# Peripherals.net
KiCad netlist of a schematic drawn in Altium Designer
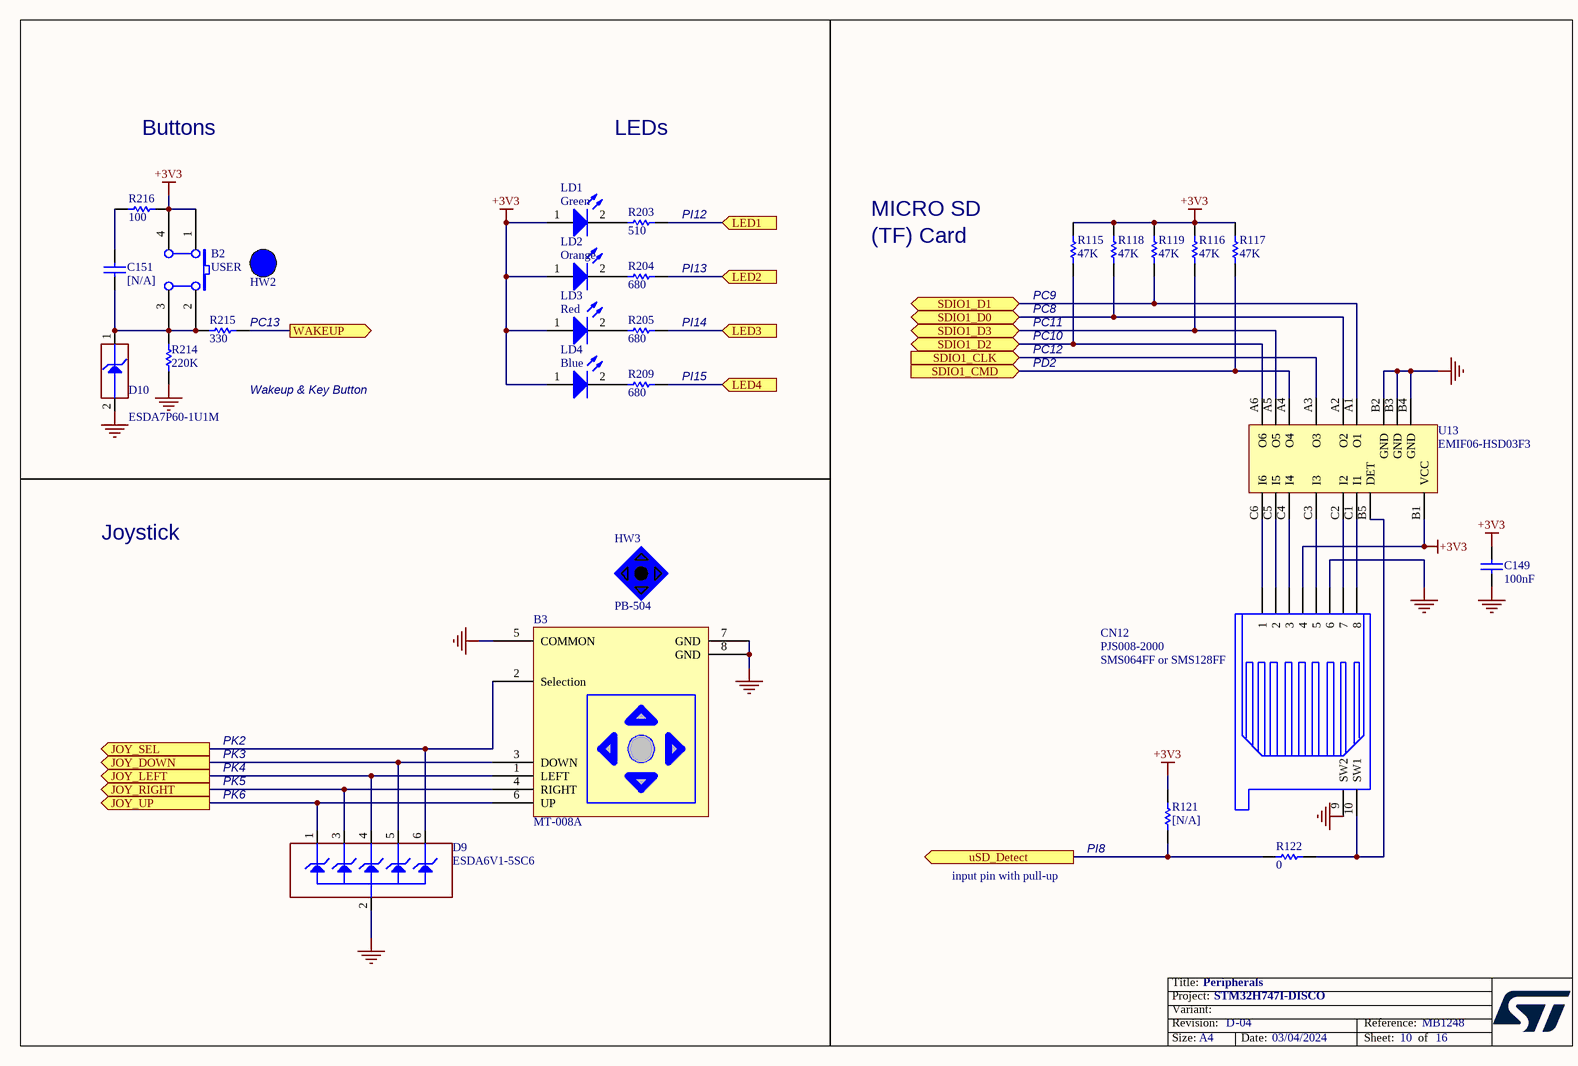
[diagram p0: Peripherals.SchDoc]

(export (version "E")
  (design (tool "Eeschema 10.0.6"))
  (components
    (comp (ref "B2")
      (value "USER")
      (footprint "PB10")
      (description "SE PUSHBUTTON")
      (libsource (lib "Documents") (part "SW PUSHBUTTON"))
    )
    (comp (ref "B3") (value "MT-008A") (footprint "MT-008A") (libsource (lib "MB1248") (part "MT-008A")))
    (comp (ref "C149")
      (value "100nF")
      (footprint "0603C")
      (description "Capacitor")
      (fields (field (name "PUBLISHER") "Altium Limited"))
      (libsource (lib "Miscellaneous Devices") (part "CAP"))
    )
    (comp (ref "C151")
      (value "[N/A]")
      (footprint "0603C")
      (description "Capacitor")
      (fields (field (name "PUBLISHER") "Altium Limited"))
      (libsource (lib "Miscellaneous Devices") (part "cap"))
    )
    (comp (ref "CN12")
      (value "PJS008-2000")
      (footprint "MSD_PJS008_")
      (libsource (lib "MB525") (part "SMS016AFA5E"))
    )
    (comp (ref "D9")
      (value "ESDA6V1-5SC6")
      (footprint "STM-SMEE:SOT23-6L")
      (description "5-line ESD protection")
      (libsource (lib "MB1248_1") (part "ESDA6V1-5SC6"))
    )
    (comp (ref "D10")
      (value "ESDA7P60-1U1M")
      (footprint "DO_2SM_1R6X1_21")
      (description "Dual Transil array for ESD protection")
      (libsource (lib "MCD_TEMP_PCH") (part "ESDALC6V1-1U2"))
    )
    (comp (ref "HW2") (value "BUTTON_HAT_BLUE") (libsource (lib "Schlib1") (part "BUTTON_HAT_BLUE")))
    (comp (ref "HW3")
      (value "PB-504")
      (description "Joystick, Blue hat")
      (fields (field (name "INTERNAL_PART_NUMBER") "MCD-01337") (field (name "MANUFACTURER") "JIUBABA"))
      (libsource (lib "MCD_PARTS_database") (part "JOYSTICK_BLUE_HAT"))
    )
    (comp (ref "LD1")
      (value "Green")
      (footprint "0603D")
      (description "Typical RED, GREEN, YELLOW, AMBER GaAs LED")
      (fields (field (name "PUBLISHER") "Altium Limited"))
      (libsource (lib "Miscellaneous Devices") (part "LED2"))
    )
    (comp (ref "LD2")
      (value "Orange")
      (footprint "0603D")
      (description "Typical RED, GREEN, YELLOW, AMBER GaAs LED")
      (fields (field (name "PUBLISHER") "Altium Limited"))
      (libsource (lib "Miscellaneous Devices") (part "LED2"))
    )
    (comp (ref "LD3")
      (value "Red")
      (footprint "0603D")
      (description "Typical RED, GREEN, YELLOW, AMBER GaAs LED")
      (fields (field (name "PUBLISHER") "Altium Limited"))
      (libsource (lib "Miscellaneous Devices") (part "LED2"))
    )
    (comp (ref "LD4")
      (value "Blue")
      (footprint "0603D")
      (description "Typical RED, GREEN, YELLOW, AMBER GaAs LED")
      (fields (field (name "PUBLISHER") "Altium Limited"))
      (libsource (lib "Miscellaneous Devices") (part "LED2"))
    )
    (comp (ref "R115")
      (value "47K")
      (footprint "0603R")
      (description "Resistor")
      (fields (field (name "PUBLISHER") "Altium Limited"))
      (libsource (lib "Miscellaneous Devices") (part "res1"))
    )
    (comp (ref "R116")
      (value "47K")
      (footprint "0603R")
      (description "Resistor")
      (fields (field (name "PUBLISHER") "Altium Limited"))
      (libsource (lib "Miscellaneous Devices") (part "res1"))
    )
    (comp (ref "R117")
      (value "47K")
      (footprint "0603R")
      (description "Resistor")
      (fields (field (name "PUBLISHER") "Altium Limited"))
      (libsource (lib "Miscellaneous Devices") (part "res1"))
    )
    (comp (ref "R118")
      (value "47K")
      (footprint "0603R")
      (description "Resistor")
      (fields (field (name "PUBLISHER") "Altium Limited"))
      (libsource (lib "Miscellaneous Devices") (part "res1"))
    )
    (comp (ref "R119")
      (value "47K")
      (footprint "0603R")
      (description "Resistor")
      (fields (field (name "PUBLISHER") "Altium Limited"))
      (libsource (lib "Miscellaneous Devices") (part "res1"))
    )
    (comp (ref "R121")
      (value "[N/A]")
      (footprint "0603R")
      (description "Resistor")
      (fields (field (name "PUBLISHER") "Altium Limited"))
      (libsource (lib "Miscellaneous Devices") (part "res1"))
    )
    (comp (ref "R122")
      (value "0")
      (footprint "0603R")
      (description "Resistor")
      (fields (field (name "PUBLISHER") "Altium Limited"))
      (libsource (lib "Miscellaneous Devices") (part "Res1"))
    )
    (comp (ref "R203")
      (value "510")
      (footprint "0603R")
      (description "Resistor")
      (fields (field (name "PUBLISHER") "Altium Limited"))
      (libsource (lib "Miscellaneous Devices") (part "Res1"))
    )
    (comp (ref "R204")
      (value "680")
      (footprint "0603R")
      (description "Resistor")
      (fields (field (name "PUBLISHER") "Altium Limited"))
      (libsource (lib "Miscellaneous Devices") (part "Res1"))
    )
    (comp (ref "R205")
      (value "680")
      (footprint "0603R")
      (description "Resistor")
      (fields (field (name "PUBLISHER") "Altium Limited"))
      (libsource (lib "Miscellaneous Devices") (part "Res1"))
    )
    (comp (ref "R209")
      (value "680")
      (footprint "0603R")
      (description "Resistor")
      (fields (field (name "PUBLISHER") "Altium Limited"))
      (libsource (lib "Miscellaneous Devices") (part "Res1"))
    )
    (comp (ref "R214")
      (value "220K")
      (footprint "0603R")
      (description "Resistor")
      (fields (field (name "PUBLISHER") "Altium Limited"))
      (libsource (lib "Miscellaneous Devices") (part "res1"))
    )
    (comp (ref "R215")
      (value "330")
      (footprint "0603R")
      (description "Resistor")
      (fields (field (name "PUBLISHER") "Altium Limited"))
      (libsource (lib "Miscellaneous Devices") (part "Res1"))
    )
    (comp (ref "R216")
      (value "100")
      (footprint "0603R")
      (description "Resistor")
      (fields (field (name "PUBLISHER") "Altium Limited"))
      (libsource (lib "Miscellaneous Devices") (part "Res1"))
    )
    (comp (ref "U13")
      (value "EMIF06-HSD03F3")
      (footprint "FBGA17_0R4_1R1X2R4")
      (description "EMI filter with integrated ESD protection for micro-SD Card™")
      (libsource (lib "MB1248_1") (part "EMIF06-HSD03F3"))
    )
  )
  (nets
    (net (code "1") (name "+3V3") (class "Default")
      (node (ref "B2") (pin "1") (pinfunction "A0_1") (pintype "passive"))
      (node (ref "B2") (pin "4") (pinfunction "A1_4") (pintype "passive"))
      (node (ref "C149") (pin "1") (pinfunction "1_1") (pintype "passive"))
      (node (ref "CN12") (pin "4") (pinfunction "4_4") (pintype "passive"))
      (node (ref "LD1") (pin "1") (pinfunction "A_1") (pintype "passive"))
      (node (ref "LD2") (pin "1") (pinfunction "A_1") (pintype "passive"))
      (node (ref "LD3") (pin "1") (pinfunction "A_1") (pintype "passive"))
      (node (ref "LD4") (pin "1") (pinfunction "A_1") (pintype "passive"))
      (node (ref "R115") (pin "1") (pinfunction "1_1") (pintype "passive"))
      (node (ref "R116") (pin "1") (pinfunction "1_1") (pintype "passive"))
      (node (ref "R117") (pin "1") (pinfunction "1_1") (pintype "passive"))
      (node (ref "R118") (pin "1") (pinfunction "1_1") (pintype "passive"))
      (node (ref "R119") (pin "1") (pinfunction "1_1") (pintype "passive"))
      (node (ref "R121") (pin "2") (pinfunction "2_2") (pintype "passive"))
      (node (ref "R216") (pin "1") (pinfunction "1_1") (pintype "passive"))
      (node (ref "U13") (pin "B1") (pinfunction "VCC_B1") (pintype "passive"))
    )
    (net (code "2") (name "/JOY_DOWN") (class "Default")
      (node (ref "B3") (pin "3") (pinfunction "DOWN_3") (pintype "passive"))
      (node (ref "D9") (pin "5") (pinfunction "IO4_5") (pintype "passive"))
    )
    (net (code "3") (name "/JOY_LEFT") (class "Default")
      (node (ref "B3") (pin "1") (pinfunction "LEFT_1") (pintype "passive"))
      (node (ref "D9") (pin "4") (pinfunction "IO3_4") (pintype "passive"))
    )
    (net (code "4") (name "/JOY_RIGHT") (class "Default")
      (node (ref "B3") (pin "4") (pinfunction "RIGHT_4") (pintype "passive"))
      (node (ref "D9") (pin "3") (pinfunction "IO2_3") (pintype "passive"))
    )
    (net (code "5") (name "/JOY_SEL") (class "Default")
      (node (ref "B3") (pin "2") (pinfunction "Selection_2") (pintype "passive"))
      (node (ref "D9") (pin "6") (pinfunction "IO5_6") (pintype "passive"))
    )
    (net (code "6") (name "/JOY_UP") (class "Default")
      (node (ref "B3") (pin "6") (pinfunction "UP_6") (pintype "passive"))
      (node (ref "D9") (pin "1") (pinfunction "IO1_1") (pintype "passive"))
    )
    (net (code "7") (name "/LED1") (class "Default")
      (node (ref "R203") (pin "1") (pinfunction "1_1") (pintype "passive"))
    )
    (net (code "8") (name "/LED2") (class "Default")
      (node (ref "R204") (pin "1") (pinfunction "1_1") (pintype "passive"))
    )
    (net (code "9") (name "/LED3") (class "Default")
      (node (ref "R205") (pin "1") (pinfunction "1_1") (pintype "passive"))
    )
    (net (code "10") (name "/LED4") (class "Default")
      (node (ref "R209") (pin "1") (pinfunction "1_1") (pintype "passive"))
    )
    (net (code "11") (name "/SDIO1_CLK") (class "Default")
      (node (ref "U13") (pin "A3") (pinfunction "O3_A3") (pintype "passive"))
    )
    (net (code "12") (name "/SDIO1_CMD") (class "Default")
      (node (ref "R117") (pin "2") (pinfunction "2_2") (pintype "passive"))
      (node (ref "U13") (pin "A4") (pinfunction "O4_A4") (pintype "passive"))
    )
    (net (code "13") (name "/SDIO1_D0") (class "Default")
      (node (ref "R118") (pin "2") (pinfunction "2_2") (pintype "passive"))
      (node (ref "U13") (pin "A2") (pinfunction "O2_A2") (pintype "passive"))
    )
    (net (code "14") (name "/SDIO1_D1") (class "Default")
      (node (ref "R119") (pin "2") (pinfunction "2_2") (pintype "passive"))
      (node (ref "U13") (pin "A1") (pinfunction "O1_A1") (pintype "passive"))
    )
    (net (code "15") (name "/SDIO1_D2") (class "Default")
      (node (ref "R115") (pin "2") (pinfunction "2_2") (pintype "passive"))
      (node (ref "U13") (pin "A6") (pinfunction "O6_A6") (pintype "passive"))
    )
    (net (code "16") (name "/SDIO1_D3") (class "Default")
      (node (ref "R116") (pin "2") (pinfunction "2_2") (pintype "passive"))
      (node (ref "U13") (pin "A5") (pinfunction "O5_A5") (pintype "passive"))
    )
    (net (code "17") (name "/WAKEUP") (class "Default")
      (node (ref "R215") (pin "2") (pinfunction "2_2") (pintype "passive"))
    )
    (net (code "18") (name "/uSD_Detect") (class "Default")
      (node (ref "R121") (pin "1") (pinfunction "1_1") (pintype "passive"))
      (node (ref "R122") (pin "1") (pinfunction "1_1") (pintype "passive"))
    )
    (net (code "19") (name "GND") (class "Default")
      (node (ref "B3") (pin "5") (pinfunction "COMMON_5") (pintype "passive"))
      (node (ref "B3") (pin "7") (pinfunction "GND_7") (pintype "passive"))
      (node (ref "B3") (pin "8") (pinfunction "GND_8") (pintype "passive"))
      (node (ref "C149") (pin "2") (pinfunction "2_2") (pintype "passive"))
      (node (ref "CN12") (pin "6") (pinfunction "6_6") (pintype "passive"))
      (node (ref "CN12") (pin "9") (pinfunction "SW2_9") (pintype "passive"))
      (node (ref "D10") (pin "2") (pinfunction "GND_2") (pintype "passive"))
      (node (ref "D9") (pin "2") (pinfunction "GND_2") (pintype "passive"))
      (node (ref "R214") (pin "2") (pinfunction "2_2") (pintype "passive"))
      (node (ref "U13") (pin "B2") (pinfunction "GND_B2") (pintype "passive"))
      (node (ref "U13") (pin "B3") (pinfunction "GND_B3") (pintype "passive"))
      (node (ref "U13") (pin "B4") (pinfunction "GND_B4") (pintype "passive"))
    )
    (net (code "20") (name "Net-(B2-B0)") (class "Default")
      (node (ref "B2") (pin "2") (pinfunction "B0_2") (pintype "passive"))
      (node (ref "B2") (pin "3") (pinfunction "B1_3") (pintype "passive"))
      (node (ref "C151") (pin "1") (pinfunction "1_1") (pintype "passive"))
      (node (ref "D10") (pin "1") (pinfunction "IO1_1") (pintype "passive"))
      (node (ref "R214") (pin "1") (pinfunction "1_1") (pintype "passive"))
      (node (ref "R215") (pin "1") (pinfunction "1_1") (pintype "passive"))
    )
    (net (code "21") (name "Net-(C151-Pad2)") (class "Default")
      (node (ref "C151") (pin "2") (pinfunction "2_2") (pintype "passive"))
      (node (ref "R216") (pin "2") (pinfunction "2_2") (pintype "passive"))
    )
    (net (code "22") (name "Net-(CN12-SW1)") (class "Default")
      (node (ref "CN12") (pin "10") (pinfunction "SW1_10") (pintype "passive"))
      (node (ref "R122") (pin "2") (pinfunction "2_2") (pintype "passive"))
      (node (ref "U13") (pin "B5") (pinfunction "DET_B5") (pintype "passive"))
    )
    (net (code "23") (name "Net-(LD1-K)") (class "Default")
      (node (ref "LD1") (pin "2") (pinfunction "K_2") (pintype "passive"))
      (node (ref "R203") (pin "2") (pinfunction "2_2") (pintype "passive"))
    )
    (net (code "24") (name "Net-(LD2-K)") (class "Default")
      (node (ref "LD2") (pin "2") (pinfunction "K_2") (pintype "passive"))
      (node (ref "R204") (pin "2") (pinfunction "2_2") (pintype "passive"))
    )
    (net (code "25") (name "Net-(LD3-K)") (class "Default")
      (node (ref "LD3") (pin "2") (pinfunction "K_2") (pintype "passive"))
      (node (ref "R205") (pin "2") (pinfunction "2_2") (pintype "passive"))
    )
    (net (code "26") (name "Net-(LD4-K)") (class "Default")
      (node (ref "LD4") (pin "2") (pinfunction "K_2") (pintype "passive"))
      (node (ref "R209") (pin "2") (pinfunction "2_2") (pintype "passive"))
    )
    (net (code "27") (name "Net-(U13-I1)") (class "Default")
      (node (ref "CN12") (pin "8") (pinfunction "8_8") (pintype "passive"))
      (node (ref "U13") (pin "C1") (pinfunction "I1_C1") (pintype "passive"))
    )
    (net (code "28") (name "Net-(U13-I2)") (class "Default")
      (node (ref "CN12") (pin "7") (pinfunction "7_7") (pintype "passive"))
      (node (ref "U13") (pin "C2") (pinfunction "I2_C2") (pintype "passive"))
    )
    (net (code "29") (name "Net-(U13-I3)") (class "Default")
      (node (ref "CN12") (pin "5") (pinfunction "5_5") (pintype "passive"))
      (node (ref "U13") (pin "C3") (pinfunction "I3_C3") (pintype "passive"))
    )
    (net (code "30") (name "Net-(U13-I4)") (class "Default")
      (node (ref "CN12") (pin "3") (pinfunction "3_3") (pintype "passive"))
      (node (ref "U13") (pin "C4") (pinfunction "I4_C4") (pintype "passive"))
    )
    (net (code "31") (name "Net-(U13-I5)") (class "Default")
      (node (ref "CN12") (pin "2") (pinfunction "2_2") (pintype "passive"))
      (node (ref "U13") (pin "C5") (pinfunction "I5_C5") (pintype "passive"))
    )
    (net (code "32") (name "Net-(U13-I6)") (class "Default")
      (node (ref "CN12") (pin "1") (pinfunction "1_1") (pintype "passive"))
      (node (ref "U13") (pin "C6") (pinfunction "I6_C6") (pintype "passive"))
    )
  )
)
